# UART_to_Micro_USB.net
KiCad netlist of a schematic drawn in Altium Designer
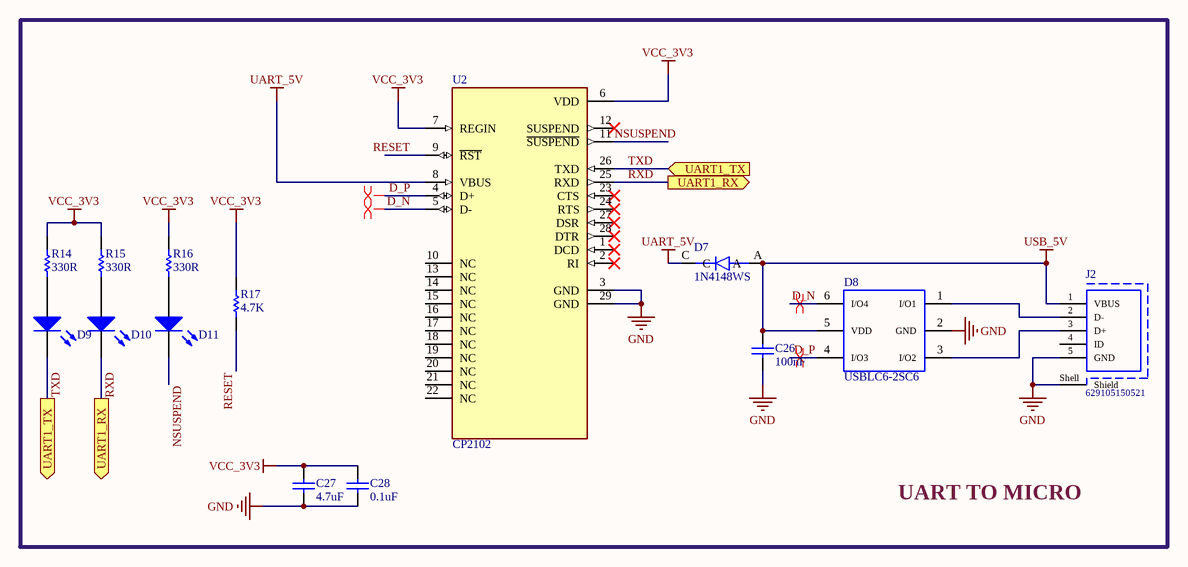
[diagram p0: UART_to_Micro_USB.SchDoc]

(export (version "E")
  (design (tool "Eeschema 10.0.6"))
  (components
    (comp (ref "C26")
      (value "100nF")
      (footprint "CAP-SM-0805")
      (description "Capacitor")
      (fields (field (name "Comment") "Cap Non-Pol SMD"))
      (libsource (lib "PIF_Library") (part "Cap Non-Pol SMD"))
    )
    (comp (ref "C27")
      (value "4.7uF")
      (footprint "CAP-SM-0805")
      (description "Capacitor")
      (fields (field (name "Comment") "Cap Non-Pol SMD"))
      (libsource (lib "PIF_Library") (part "Cap Non-Pol SMD"))
    )
    (comp (ref "C28")
      (value "0.1uF")
      (footprint "CAP-SM-0805")
      (description "Capacitor")
      (fields (field (name "Comment") "Cap Non-Pol SMD"))
      (libsource (lib "PIF_Library") (part "Cap Non-Pol SMD"))
    )
    (comp (ref "D7")
      (value "1N4148WS")
      (footprint "SODFL2512X100N")
      (description "Diode Standard 75V 300mA (DC) Surface Mount SOD-323")
      (fields (field (name "MF") "ON Semiconductor"))
      (libsource (lib "1N4148WS") (part "1N4148WS"))
    )
    (comp (ref "D8")
      (value "USBLC6-2SC6")
      (footprint "WE-TVS_SOT23-6L")
      (description "WE-TVS TVS Diode - High Speed Series, SOT23-6L, 4+1Channel, 5Vdc")
      (fields
        (field (name "MANUFACTURER PART NUMBER") "824001")
        (field (name "MANUFACTURER") "Wurth Elektronik")
      )
      (libsource (lib "Altium_WE-TVS (rev20a)") (part "824001"))
    )
    (comp (ref "D9")
      (value "LED SMD")
      (footprint "LED_0603_Blue")
      (description "LED")
      (libsource (lib "PIF_Library") (part "LED SMD"))
    )
    (comp (ref "D10")
      (value "LED SMD")
      (footprint "LED_0603_Blue")
      (description "LED")
      (libsource (lib "PIF_Library") (part "LED SMD"))
    )
    (comp (ref "D11")
      (value "LED SMD")
      (footprint "LED_0603_Blue")
      (description "LED")
      (libsource (lib "PIF_Library") (part "LED SMD"))
    )
    (comp (ref "J2")
      (value "629105150521")
      (footprint "629105150521")
      (description "Micro USB 2.0 Type B Receptacle WR-COM, Horizontal, SMT, with Pegs, High Current at Pin 1 & Pin 5")
      (fields (field (name "PUBLISHER") "Wurth Elektronik"))
      (libsource (lib "ALTIUM-WR-COM_USB_20-rev18d") (part "629105150521"))
    )
    (comp (ref "R14")
      (value "330R")
      (footprint "RES-SM-0805")
      (description "Resistor")
      (fields (field (name "Comment") "RESISTOR SMD"))
      (libsource (lib "PIF_Library") (part "RESISTOR SMD"))
    )
    (comp (ref "R15")
      (value "330R")
      (footprint "RES-SM-0805")
      (description "Resistor")
      (fields (field (name "Comment") "RESISTOR SMD"))
      (libsource (lib "PIF_Library") (part "RESISTOR SMD"))
    )
    (comp (ref "R16")
      (value "330R")
      (footprint "RES-SM-0805")
      (description "Resistor")
      (fields (field (name "Comment") "RESISTOR SMD"))
      (libsource (lib "PIF_Library") (part "RESISTOR SMD"))
    )
    (comp (ref "R17")
      (value "4.7K")
      (footprint "RES-SM-0805")
      (description "Resistor")
      (fields (field (name "Comment") "RESISTOR SMD"))
      (libsource (lib "PIF_Library") (part "RESISTOR SMD"))
    )
    (comp (ref "U2")
      (value "CP2102")
      (footprint "QFN50P500X500X100-29N")
      (description "CP2102N USB 2.0 to UART (RS232) Bridge Interface Evaluation Board")
      (fields (field (name "MF") "Silicon Labs"))
      (libsource (lib "CP2102") (part "CP2102"))
    )
  )
  (nets
    (net (code "1") (name "/D_N") (class "Default")
      (node (ref "D8") (pin "6") (pinfunction "I/O4_6") (pintype "passive"))
      (node (ref "U2") (pin "5") (pinfunction "D-_5") (pintype "bidirectional"))
    )
    (net (code "2") (name "/D_P") (class "Default")
      (node (ref "D8") (pin "4") (pinfunction "I/O3_4") (pintype "passive"))
      (node (ref "U2") (pin "4") (pinfunction "D+_4") (pintype "bidirectional"))
    )
    (net (code "3") (name "/NSUSPEND") (class "Default")
      (node (ref "D11") (pin "2") (pinfunction "K_2") (pintype "passive"))
      (node (ref "U2") (pin "11") (pinfunction "~{SUSPEND}_11") (pintype "output"))
    )
    (net (code "4") (name "/RESET") (class "Default")
      (node (ref "R17") (pin "2") (pinfunction "2_2") (pintype "passive"))
      (node (ref "U2") (pin "9") (pinfunction "~{RST}_9") (pintype "bidirectional"))
    )
    (net (code "5") (name "/RXD") (class "Default")
      (node (ref "D10") (pin "2") (pinfunction "K_2") (pintype "passive"))
      (node (ref "U2") (pin "25") (pinfunction "RXD_25") (pintype "output"))
    )
    (net (code "6") (name "/TXD") (class "Default")
      (node (ref "D9") (pin "2") (pinfunction "K_2") (pintype "passive"))
      (node (ref "U2") (pin "26") (pinfunction "TXD_26") (pintype "input"))
    )
    (net (code "7") (name "GND") (class "Default")
      (node (ref "C26") (pin "1") (pinfunction "1_1") (pintype "passive"))
      (node (ref "C27") (pin "1") (pinfunction "1_1") (pintype "passive"))
      (node (ref "C28") (pin "1") (pinfunction "1_1") (pintype "passive"))
      (node (ref "D8") (pin "2") (pinfunction "GND_2") (pintype "passive"))
      (node (ref "J2") (pin "5") (pinfunction "GND_5") (pintype "passive"))
      (node (ref "J2") (pin "Shell") (pinfunction "Shield_Shell") (pintype "passive"))
      (node (ref "U2") (pin "29") (pinfunction "GND_29") (pintype "power_in"))
      (node (ref "U2") (pin "3") (pinfunction "GND_3") (pintype "power_in"))
    )
    (net (code "8") (name "Net-(D8-I{slash}O1)") (class "Default")
      (node (ref "D8") (pin "1") (pinfunction "I/O1_1") (pintype "passive"))
      (node (ref "J2") (pin "2") (pinfunction "D-_2") (pintype "passive"))
    )
    (net (code "9") (name "Net-(D8-I{slash}O2)") (class "Default")
      (node (ref "D8") (pin "3") (pinfunction "I/O2_3") (pintype "passive"))
      (node (ref "J2") (pin "3") (pinfunction "D+_3") (pintype "passive"))
    )
    (net (code "10") (name "Net-(D9-A)") (class "Default")
      (node (ref "D9") (pin "1") (pinfunction "A_1") (pintype "passive"))
      (node (ref "R14") (pin "1") (pinfunction "1_1") (pintype "passive"))
    )
    (net (code "11") (name "Net-(D10-A)") (class "Default")
      (node (ref "D10") (pin "1") (pinfunction "A_1") (pintype "passive"))
      (node (ref "R15") (pin "1") (pinfunction "1_1") (pintype "passive"))
    )
    (net (code "12") (name "Net-(D11-A)") (class "Default")
      (node (ref "D11") (pin "1") (pinfunction "A_1") (pintype "passive"))
      (node (ref "R16") (pin "1") (pinfunction "1_1") (pintype "passive"))
    )
    (net (code "13") (name "UART_5V") (class "Default")
      (node (ref "D7") (pin "C") (pinfunction "C_C") (pintype "passive"))
      (node (ref "U2") (pin "8") (pinfunction "VBUS_8") (pintype "input"))
    )
    (net (code "14") (name "USB_5V") (class "Default")
      (node (ref "C26") (pin "2") (pinfunction "2_2") (pintype "passive"))
      (node (ref "D7") (pin "A") (pinfunction "A_A") (pintype "passive"))
      (node (ref "D8") (pin "5") (pinfunction "VDD_5") (pintype "passive"))
      (node (ref "J2") (pin "1") (pinfunction "VBUS_1") (pintype "passive"))
    )
    (net (code "15") (name "VCC_3V3") (class "Default")
      (node (ref "C27") (pin "2") (pinfunction "2_2") (pintype "passive"))
      (node (ref "C28") (pin "2") (pinfunction "2_2") (pintype "passive"))
      (node (ref "R14") (pin "2") (pinfunction "2_2") (pintype "passive"))
      (node (ref "R15") (pin "2") (pinfunction "2_2") (pintype "passive"))
      (node (ref "R16") (pin "2") (pinfunction "2_2") (pintype "passive"))
      (node (ref "R17") (pin "1") (pinfunction "1_1") (pintype "passive"))
      (node (ref "U2") (pin "6") (pinfunction "VDD_6") (pintype "power_in"))
      (node (ref "U2") (pin "7") (pinfunction "REGIN_7") (pintype "input"))
    )
    (net (code "16") (name "unconnected-(J2-ID-Pad4)") (class "Default")
      (node (ref "J2") (pin "4") (pinfunction "ID_4") (pintype "passive"))
    )
    (net (code "17") (name "unconnected-(U2-CTS-Pad23)") (class "Default")
      (node (ref "U2") (pin "23") (pinfunction "CTS_23") (pintype "input+no_connect"))
    )
    (net (code "18") (name "unconnected-(U2-DCD-Pad1)") (class "Default")
      (node (ref "U2") (pin "1") (pinfunction "DCD_1") (pintype "input+no_connect"))
    )
    (net (code "19") (name "unconnected-(U2-DSR-Pad27)") (class "Default")
      (node (ref "U2") (pin "27") (pinfunction "DSR_27") (pintype "input+no_connect"))
    )
    (net (code "20") (name "unconnected-(U2-DTR-Pad28)") (class "Default")
      (node (ref "U2") (pin "28") (pinfunction "DTR_28") (pintype "output+no_connect"))
    )
    (net (code "21") (name "unconnected-(U2-NC-Pad10)") (class "Default")
      (node (ref "U2") (pin "10") (pinfunction "NC_10") (pintype "passive"))
    )
    (net (code "22") (name "unconnected-(U2-NC-Pad13)") (class "Default")
      (node (ref "U2") (pin "13") (pinfunction "NC_13") (pintype "passive"))
    )
    (net (code "23") (name "unconnected-(U2-NC-Pad14)") (class "Default")
      (node (ref "U2") (pin "14") (pinfunction "NC_14") (pintype "passive"))
    )
    (net (code "24") (name "unconnected-(U2-NC-Pad15)") (class "Default")
      (node (ref "U2") (pin "15") (pinfunction "NC_15") (pintype "passive"))
    )
    (net (code "25") (name "unconnected-(U2-NC-Pad16)") (class "Default")
      (node (ref "U2") (pin "16") (pinfunction "NC_16") (pintype "passive"))
    )
    (net (code "26") (name "unconnected-(U2-NC-Pad17)") (class "Default")
      (node (ref "U2") (pin "17") (pinfunction "NC_17") (pintype "passive"))
    )
    (net (code "27") (name "unconnected-(U2-NC-Pad18)") (class "Default")
      (node (ref "U2") (pin "18") (pinfunction "NC_18") (pintype "passive"))
    )
    (net (code "28") (name "unconnected-(U2-NC-Pad19)") (class "Default")
      (node (ref "U2") (pin "19") (pinfunction "NC_19") (pintype "passive"))
    )
    (net (code "29") (name "unconnected-(U2-NC-Pad20)") (class "Default")
      (node (ref "U2") (pin "20") (pinfunction "NC_20") (pintype "passive"))
    )
    (net (code "30") (name "unconnected-(U2-NC-Pad21)") (class "Default")
      (node (ref "U2") (pin "21") (pinfunction "NC_21") (pintype "passive"))
    )
    (net (code "31") (name "unconnected-(U2-NC-Pad22)") (class "Default")
      (node (ref "U2") (pin "22") (pinfunction "NC_22") (pintype "passive"))
    )
    (net (code "32") (name "unconnected-(U2-RI-Pad2)") (class "Default")
      (node (ref "U2") (pin "2") (pinfunction "RI_2") (pintype "input+no_connect"))
    )
    (net (code "33") (name "unconnected-(U2-RTS-Pad24)") (class "Default")
      (node (ref "U2") (pin "24") (pinfunction "RTS_24") (pintype "output+no_connect"))
    )
    (net (code "34") (name "unconnected-(U2-SUSPEND-Pad12)") (class "Default")
      (node (ref "U2") (pin "12") (pinfunction "SUSPEND_12") (pintype "output+no_connect"))
    )
  )
)
